# MicroLock_PassThrough.net
KiCad netlist of a schematic drawn in EAGLE
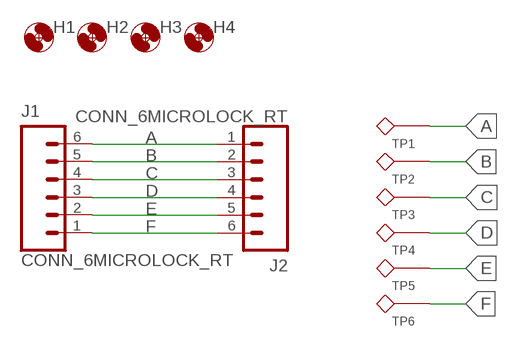
[diagram p0: schematic, sheet 1]

(export (version "E")
  (design (tool "Eeschema 10.0.6"))
  (components
    (comp (ref "H1")
      (value "MOUNTING_HOLE2_NP")
      (footprint "eagle-import:2_56")
      (fields (field (name "MPN") "DNP"))
      (libsource (lib "eagle-import") (part "MOUNTING_HOLE2_NP"))
    )
    (comp (ref "H2")
      (value "MOUNTING_HOLE2_NP")
      (footprint "eagle-import:2_56")
      (fields (field (name "MPN") "DNP"))
      (libsource (lib "eagle-import") (part "MOUNTING_HOLE2_NP"))
    )
    (comp (ref "H3")
      (value "MOUNTING_HOLE2_NP")
      (footprint "eagle-import:2_56")
      (fields (field (name "MPN") "DNP"))
      (libsource (lib "eagle-import") (part "MOUNTING_HOLE2_NP"))
    )
    (comp (ref "H4")
      (value "MOUNTING_HOLE2_NP")
      (footprint "eagle-import:2_56")
      (fields (field (name "MPN") "DNP"))
      (libsource (lib "eagle-import") (part "MOUNTING_HOLE2_NP"))
    )
    (comp (ref "J1")
      (value "CONN_6MICROLOCK_RT")
      (footprint "eagle-import:1X06_MICROLOCKPLUS_RT")
      (fields (field (name "MF") "Molex") (field (name "MPN") "5055670681"))
      (libsource (lib "eagle-import") (part "CONN_6MICROLOCK_RT"))
    )
    (comp (ref "J2")
      (value "CONN_6MICROLOCK_RT")
      (footprint "eagle-import:1X06_MICROLOCKPLUS_RT")
      (fields (field (name "MF") "Molex") (field (name "MPN") "5055670681"))
      (libsource (lib "eagle-import") (part "CONN_6MICROLOCK_RT"))
    )
    (comp (ref "TP1")
      (value "TESTPOINTRCU")
      (footprint "eagle-import:TESTPOINT_0603")
      (fields (field (name "MF") "TE Connectivity") (field (name "MPN") "RCU-0C"))
      (libsource (lib "eagle-import") (part "TESTPOINTRCU"))
    )
    (comp (ref "TP2")
      (value "TESTPOINTRCU")
      (footprint "eagle-import:TESTPOINT_0603")
      (fields (field (name "MF") "TE Connectivity") (field (name "MPN") "RCU-0C"))
      (libsource (lib "eagle-import") (part "TESTPOINTRCU"))
    )
    (comp (ref "TP3")
      (value "TESTPOINTRCU")
      (footprint "eagle-import:TESTPOINT_0603")
      (fields (field (name "MF") "TE Connectivity") (field (name "MPN") "RCU-0C"))
      (libsource (lib "eagle-import") (part "TESTPOINTRCU"))
    )
    (comp (ref "TP4")
      (value "TESTPOINTRCU")
      (footprint "eagle-import:TESTPOINT_0603")
      (fields (field (name "MF") "TE Connectivity") (field (name "MPN") "RCU-0C"))
      (libsource (lib "eagle-import") (part "TESTPOINTRCU"))
    )
    (comp (ref "TP5")
      (value "TESTPOINTRCU")
      (footprint "eagle-import:TESTPOINT_0603")
      (fields (field (name "MF") "TE Connectivity") (field (name "MPN") "RCU-0C"))
      (libsource (lib "eagle-import") (part "TESTPOINTRCU"))
    )
    (comp (ref "TP6")
      (value "TESTPOINTRCU")
      (footprint "eagle-import:TESTPOINT_0603")
      (fields (field (name "MF") "TE Connectivity") (field (name "MPN") "RCU-0C"))
      (libsource (lib "eagle-import") (part "TESTPOINTRCU"))
    )
  )
  (nets
    (net (code "1") (name "A") (class "Default")
      (node (ref "J1") (pin "6") (pinfunction "6_6") (pintype "passive"))
      (node (ref "J2") (pin "1") (pinfunction "1_1") (pintype "passive"))
      (node (ref "TP1") (pin "1") (pinfunction "P$1_1") (pintype "bidirectional"))
    )
    (net (code "2") (name "B") (class "Default")
      (node (ref "J1") (pin "5") (pinfunction "5_5") (pintype "passive"))
      (node (ref "J2") (pin "2") (pinfunction "2_2") (pintype "passive"))
      (node (ref "TP2") (pin "1") (pinfunction "P$1_1") (pintype "bidirectional"))
    )
    (net (code "3") (name "C") (class "Default")
      (node (ref "J1") (pin "4") (pinfunction "4_4") (pintype "passive"))
      (node (ref "J2") (pin "3") (pinfunction "3_3") (pintype "passive"))
      (node (ref "TP3") (pin "1") (pinfunction "P$1_1") (pintype "bidirectional"))
    )
    (net (code "4") (name "D") (class "Default")
      (node (ref "J1") (pin "3") (pinfunction "3_3") (pintype "passive"))
      (node (ref "J2") (pin "4") (pinfunction "4_4") (pintype "passive"))
      (node (ref "TP4") (pin "1") (pinfunction "P$1_1") (pintype "bidirectional"))
    )
    (net (code "5") (name "E") (class "Default")
      (node (ref "J1") (pin "2") (pinfunction "2_2") (pintype "passive"))
      (node (ref "J2") (pin "5") (pinfunction "5_5") (pintype "passive"))
      (node (ref "TP5") (pin "1") (pinfunction "P$1_1") (pintype "bidirectional"))
    )
    (net (code "6") (name "F") (class "Default")
      (node (ref "J1") (pin "1") (pinfunction "1_1") (pintype "passive"))
      (node (ref "J2") (pin "6") (pinfunction "6_6") (pintype "passive"))
      (node (ref "TP6") (pin "1") (pinfunction "P$1_1") (pintype "bidirectional"))
    )
  )
)
